# Sheet1.net
KiCad netlist of a schematic drawn in Altium Designer
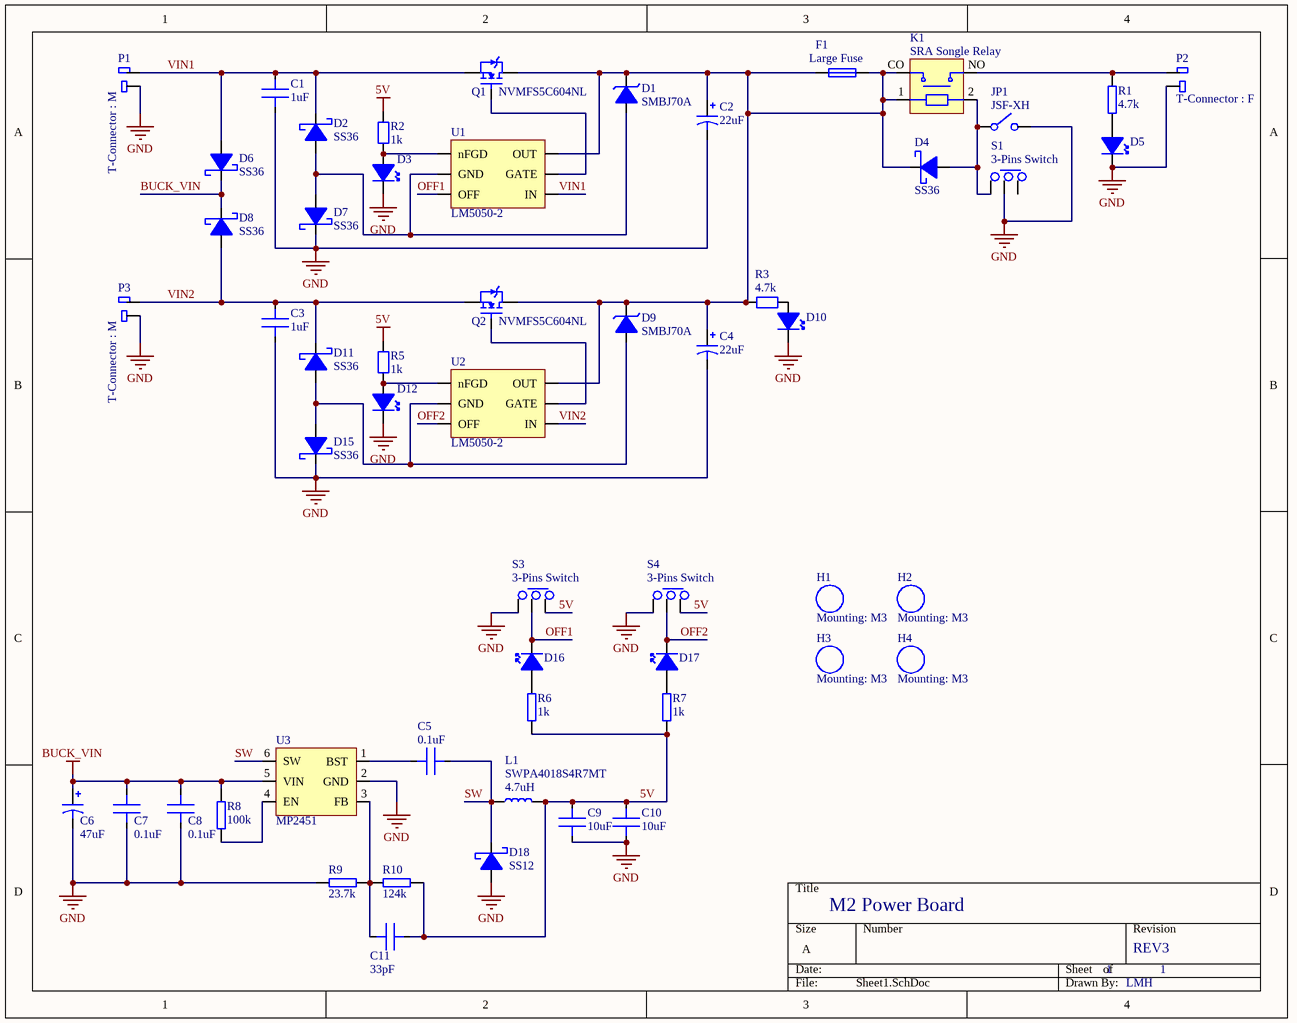
[diagram p0: Sheet1.SchDoc]

(export (version "E")
  (design (tool "Eeschema 10.0.6"))
  (components
    (comp (ref "C1")
      (value "1uF")
      (footprint "CAP 0805/2012")
      (description "Unpolarized Capacitor")
      (fields (field (name "Comment") "Cap : Unpolarized"))
      (libsource (lib "MyLib_General") (part "Cap {colon} Unpolarized"))
    )
    (comp (ref "C2")
      (value "22uF")
      (footprint "CAP AL C 5.3MM")
      (description "Polarized Capacitor")
      (fields (field (name "Comment") "Cap : Polarized"))
      (libsource (lib "") (part "Cap {colon} Polarized_1"))
    )
    (comp (ref "C3")
      (value "1uF")
      (footprint "CAP 0805/2012")
      (description "Unpolarized Capacitor")
      (fields (field (name "Comment") "Cap : Unpolarized"))
      (libsource (lib "MyLib_General") (part "Cap {colon} Unpolarized"))
    )
    (comp (ref "C4")
      (value "22uF")
      (footprint "CAP AL C 5.3MM")
      (description "Polarized Capacitor")
      (fields (field (name "Comment") "Cap : Polarized"))
      (libsource (lib "") (part "Cap {colon} Polarized_1"))
    )
    (comp (ref "C5")
      (value "0.1uF")
      (footprint "CAP 0805/2012")
      (description "Unpolarized Capacitor")
      (fields (field (name "Comment") "Cap : Unpolarized"))
      (libsource (lib "MyLib_General") (part "Cap {colon} Unpolarized"))
    )
    (comp (ref "C6")
      (value "47uF")
      (footprint "CAP AL D 6.6MM")
      (description "Polarized Capacitor")
      (fields (field (name "Comment") "Cap : Polarized"))
      (libsource (lib "MyLib_General") (part "Cap {colon} Polarized"))
    )
    (comp (ref "C7")
      (value "0.1uF")
      (footprint "CAP 0805/2012")
      (description "Unpolarized Capacitor")
      (fields (field (name "Comment") "Cap : Unpolarized"))
      (libsource (lib "MyLib_General") (part "Cap {colon} Unpolarized"))
    )
    (comp (ref "C8")
      (value "0.1uF")
      (footprint "CAP 0805/2012")
      (description "Unpolarized Capacitor")
      (fields (field (name "Comment") "Cap : Unpolarized"))
      (libsource (lib "MyLib_General") (part "Cap {colon} Unpolarized"))
    )
    (comp (ref "C9")
      (value "10uF")
      (footprint "CAP 1206/3216")
      (description "Unpolarized Capacitor")
      (fields (field (name "Comment") "Cap : Unpolarized"))
      (libsource (lib "MyLib_General") (part "Cap {colon} Unpolarized"))
    )
    (comp (ref "C10")
      (value "10uF")
      (footprint "CAP 1206/3216")
      (description "Unpolarized Capacitor")
      (fields (field (name "Comment") "Cap : Unpolarized"))
      (libsource (lib "MyLib_General") (part "Cap {colon} Unpolarized"))
    )
    (comp (ref "C11")
      (value "33pF")
      (footprint "CAP 0805/2012")
      (description "Unpolarized Capacitor")
      (fields (field (name "Comment") "Cap : Unpolarized"))
      (libsource (lib "MyLib_General") (part "Cap {colon} Unpolarized"))
    )
    (comp (ref "D1")
      (value "SMBJ70A")
      (footprint "SMB (DO-214AA)")
      (description "Transient Voltage Suppression Diodes")
      (fields (field (name "NAME") "SMBJ70A"))
      (libsource (lib "Schlib1") (part "SMBJ70A"))
    )
    (comp (ref "D2")
      (value "SS36")
      (footprint "SMA (DO-214AC)")
      (description "Surface Mount Schottky Barrier Rectifier")
      (fields (field (name "NAME") "SS36"))
      (libsource (lib "Schlib1") (part "SS36"))
    )
    (comp (ref "D3") (value "LED") (footprint "LED 0805/2012") (libsource (lib "MyLib_General") (part "LED")))
    (comp (ref "D4")
      (value "SS36")
      (footprint "SMA (DO-214AC)")
      (description "Surface Mount Schottky Barrier Rectifier")
      (fields (field (name "NAME") "SS36"))
      (libsource (lib "Schlib1") (part "SS36"))
    )
    (comp (ref "D5") (value "LED") (footprint "LED 0805/2012") (libsource (lib "MyLib_General") (part "LED")))
    (comp (ref "D6")
      (value "SS36")
      (footprint "SMA (DO-214AC)")
      (description "Surface Mount Schottky Barrier Rectifier")
      (fields (field (name "NAME") "SS36"))
      (libsource (lib "Schlib1") (part "SS36"))
    )
    (comp (ref "D7")
      (value "SS36")
      (footprint "SMA (DO-214AC)")
      (description "Surface Mount Schottky Barrier Rectifier")
      (fields (field (name "NAME") "SS36"))
      (libsource (lib "Schlib1") (part "SS36"))
    )
    (comp (ref "D8")
      (value "SS36")
      (footprint "SMA (DO-214AC)")
      (description "Surface Mount Schottky Barrier Rectifier")
      (fields (field (name "NAME") "SS36"))
      (libsource (lib "Schlib1") (part "SS36"))
    )
    (comp (ref "D9")
      (value "SMBJ70A")
      (footprint "SMB (DO-214AA)")
      (description "Transient Voltage Suppression Diodes")
      (fields (field (name "NAME") "SMBJ70A"))
      (libsource (lib "Schlib1") (part "SMBJ70A"))
    )
    (comp (ref "D10")
      (value "LED")
      (footprint "LED 0805/2012")
      (libsource (lib "MyLib_General") (part "LED"))
    )
    (comp (ref "D11")
      (value "SS36")
      (footprint "SMA (DO-214AC)")
      (description "Surface Mount Schottky Barrier Rectifier")
      (fields (field (name "NAME") "SS36"))
      (libsource (lib "Schlib1") (part "SS36"))
    )
    (comp (ref "D12")
      (value "LED")
      (footprint "LED 0805/2012")
      (libsource (lib "MyLib_General") (part "LED"))
    )
    (comp (ref "D15")
      (value "SS36")
      (footprint "SMA (DO-214AC)")
      (description "Surface Mount Schottky Barrier Rectifier")
      (fields (field (name "NAME") "SS36"))
      (libsource (lib "Schlib1") (part "SS36"))
    )
    (comp (ref "D16")
      (value "LED")
      (footprint "LED 0805/2012")
      (libsource (lib "MyLib_General") (part "LED"))
    )
    (comp (ref "D17")
      (value "LED")
      (footprint "LED 0805/2012")
      (libsource (lib "MyLib_General") (part "LED"))
    )
    (comp (ref "D18")
      (value "SS12")
      (footprint "SMA (DO-214AC)")
      (description "Surface Mount Schottky Barrier Rectifier")
      (fields (field (name "NAME") "SS12"))
      (libsource (lib "Schlib1") (part "SS12"))
    )
    (comp (ref "F1")
      (value "Large Fuse")
      (footprint "Fuse")
      (description "Large size fuse")
      (libsource (lib "Schlib1") (part "Large Fuse"))
    )
    (comp (ref "H1")
      (value "Mounting: M3")
      (footprint "Mounting hole M3")
      (description "Mounting Hole: M3")
      (libsource (lib "MyLib_General") (part "Mounting{colon} M3"))
    )
    (comp (ref "H2")
      (value "Mounting: M3")
      (footprint "Mounting hole M3")
      (description "Mounting Hole: M3")
      (libsource (lib "MyLib_General") (part "Mounting{colon} M3"))
    )
    (comp (ref "H3")
      (value "Mounting: M3")
      (footprint "Mounting hole M3")
      (description "Mounting Hole: M3")
      (libsource (lib "MyLib_General") (part "Mounting{colon} M3"))
    )
    (comp (ref "H4")
      (value "Mounting: M3")
      (footprint "Mounting hole M3")
      (description "Mounting Hole: M3")
      (libsource (lib "MyLib_General") (part "Mounting{colon} M3"))
    )
    (comp (ref "JP1")
      (value "2-Pins Header")
      (footprint "2-Pins Header")
      (fields (field (name "NAME") "JSF-XH"))
      (libsource (lib "Schlib1") (part "2-Pins Header"))
    )
    (comp (ref "K1")
      (value "SRA Songle Relay")
      (footprint "SRA Songle Relay")
      (description "20A Relay")
      (libsource (lib "Schlib1") (part "SRA Songle Relay"))
    )
    (comp (ref "L1")
      (value "SWPA4018S4R7MT")
      (footprint "SWPA4018S4R7MT")
      (description "Wire Wound SMD Power Inductor ; 4.7uH ; 1.7A")
      (fields (field (name "ALTIUM_VALUE") "4.7uH"))
      (libsource (lib "Schlib1") (part "SWPA4018S4R7MT"))
    )
    (comp (ref "P1")
      (value "T-Connector : M")
      (footprint "T CONNECTOR M")
      (description "T-shape connector ; Male side")
      (fields (field (name "NAME") "T-Connector : M"))
      (libsource (lib "MyLib_General") (part "T-Connector {colon} M"))
    )
    (comp (ref "P2")
      (value "T-Connector : F")
      (footprint "T CONNECTOR F")
      (description "T-shape connector ; Female side")
      (fields (field (name "NAME") "T-Connector : F"))
      (libsource (lib "MyLib_General") (part "T-Connector {colon} F"))
    )
    (comp (ref "P3")
      (value "T-Connector : M")
      (footprint "T CONNECTOR M")
      (description "T-shape connector ; Male side")
      (fields (field (name "NAME") "T-Connector : M"))
      (libsource (lib "MyLib_General") (part "T-Connector {colon} M"))
    )
    (comp (ref "Q1")
      (value "NVMFS5C604NL")
      (footprint "NVMFS5C604NL")
      (description "Power MOSFET ; 60 V ; 1.2 mR ; 287A ; Single N−Channel")
      (fields (field (name "NAME") "NVMFS5C604NL"))
      (libsource (lib "Schlib1") (part "NVMFS5C604NL"))
    )
    (comp (ref "Q2")
      (value "NVMFS5C604NL")
      (footprint "NVMFS5C604NL")
      (description "Power MOSFET ; 60 V ; 1.2 mR ; 287A ; Single N−Channel")
      (fields (field (name "NAME") "NVMFS5C604NL"))
      (libsource (lib "Schlib1") (part "NVMFS5C604NL"))
    )
    (comp (ref "R1")
      (value "4.7k")
      (footprint "RES 0805/2012")
      (description "Resistor")
      (fields (field (name "Comment") "Res"))
      (libsource (lib "MyLib_General") (part "Res"))
    )
    (comp (ref "R2")
      (value "1k")
      (footprint "RES 0805/2012")
      (description "Resistor")
      (fields (field (name "Comment") "Res"))
      (libsource (lib "") (part "Res_1"))
    )
    (comp (ref "R3")
      (value "4.7k")
      (footprint "RES 0805/2012")
      (description "Resistor")
      (fields (field (name "Comment") "Res"))
      (libsource (lib "") (part "Res_1"))
    )
    (comp (ref "R5")
      (value "1k")
      (footprint "RES 0805/2012")
      (description "Resistor")
      (fields (field (name "Comment") "Res"))
      (libsource (lib "") (part "Res_1"))
    )
    (comp (ref "R6")
      (value "1k")
      (footprint "RES 0805/2012")
      (description "Resistor")
      (fields (field (name "Comment") "Res"))
      (libsource (lib "MyLib_General") (part "Res"))
    )
    (comp (ref "R7")
      (value "1k")
      (footprint "RES 0805/2012")
      (description "Resistor")
      (fields (field (name "Comment") "Res"))
      (libsource (lib "MyLib_General") (part "Res"))
    )
    (comp (ref "R8")
      (value "100k")
      (footprint "RES 0805/2012")
      (description "Resistor")
      (fields (field (name "Comment") "Res"))
      (libsource (lib "MyLib_General") (part "Res"))
    )
    (comp (ref "R9")
      (value "23.7k")
      (footprint "RES 0805/2012")
      (description "Resistor")
      (fields (field (name "Comment") "Res"))
      (libsource (lib "MyLib_General") (part "Res"))
    )
    (comp (ref "R10")
      (value "124k")
      (footprint "RES 0805/2012")
      (description "Resistor")
      (fields (field (name "Comment") "Res"))
      (libsource (lib "MyLib_General") (part "Res"))
    )
    (comp (ref "S1")
      (value "3-Pins Switch")
      (footprint "3-Pins Switch")
      (description "SS12d00G3")
      (fields (field (name "NAME") "3-Pins Switch"))
      (libsource (lib "Schlib1") (part "3-Pins Switch"))
    )
    (comp (ref "S3")
      (value "3-Pins Switch")
      (footprint "3-Pins Switch")
      (description "SS12d00G3")
      (fields (field (name "NAME") "3-Pins Switch"))
      (libsource (lib "Schlib1") (part "3-Pins Switch"))
    )
    (comp (ref "S4")
      (value "3-Pins Switch")
      (footprint "3-Pins Switch")
      (description "SS12d00G3")
      (fields (field (name "NAME") "3-Pins Switch"))
      (libsource (lib "Schlib1") (part "3-Pins Switch"))
    )
    (comp (ref "U1")
      (value "LM5050-2")
      (footprint "SOT23-6")
      (description "High-Side OR-ing FET Controller")
      (fields (field (name "NAME") "LM5050-2"))
      (libsource (lib "Schlib1") (part "LM5050-2"))
    )
    (comp (ref "U2")
      (value "LM5050-2")
      (footprint "SOT23-6")
      (description "High-Side OR-ing FET Controller")
      (fields (field (name "NAME") "LM5050-2"))
      (libsource (lib "Schlib1") (part "LM5050-2"))
    )
    (comp (ref "U3")
      (value "MP2451")
      (footprint "SOT23-6")
      (description "Step-Down Converter ; 36V ; 2MHz ; 0.6A")
      (fields (field (name "NAME") "MP2451"))
      (libsource (lib "Schlib1") (part "MP2451"))
    )
  )
  (nets
    (net (code "1") (name "/OFF1") (class "Default")
      (node (ref "D16") (pin "K") (pinfunction "K_K") (pintype "passive"))
      (node (ref "S3") (pin "2") (pintype "passive"))
      (node (ref "U1") (pin "3") (pinfunction "OFF_3") (pintype "passive"))
    )
    (net (code "2") (name "/OFF2") (class "Default")
      (node (ref "D17") (pin "K") (pinfunction "K_K") (pintype "passive"))
      (node (ref "S4") (pin "2") (pintype "passive"))
      (node (ref "U2") (pin "3") (pinfunction "OFF_3") (pintype "passive"))
    )
    (net (code "3") (name "/SW") (class "Default")
      (node (ref "C5") (pin "2") (pinfunction "2_2") (pintype "passive"))
      (node (ref "D18") (pin "K") (pinfunction "K_K") (pintype "passive"))
      (node (ref "L1") (pin "1") (pinfunction "1_1") (pintype "passive"))
      (node (ref "U3") (pin "6") (pinfunction "SW_6") (pintype "passive"))
    )
    (net (code "4") (name "/VIN1") (class "Default")
      (node (ref "C1") (pin "2") (pinfunction "2_2") (pintype "passive"))
      (node (ref "D2") (pin "K") (pinfunction "K_K") (pintype "passive"))
      (node (ref "D6") (pin "A") (pinfunction "A_A") (pintype "passive"))
      (node (ref "P1") (pin "P") (pinfunction "2_P") (pintype "passive"))
      (node (ref "Q1") (pin "S") (pinfunction "S_S") (pintype "passive"))
      (node (ref "U1") (pin "4") (pinfunction "IN_4") (pintype "passive"))
    )
    (net (code "5") (name "/VIN2") (class "Default")
      (node (ref "C3") (pin "2") (pinfunction "2_2") (pintype "passive"))
      (node (ref "D11") (pin "K") (pinfunction "K_K") (pintype "passive"))
      (node (ref "D8") (pin "A") (pinfunction "A_A") (pintype "passive"))
      (node (ref "P3") (pin "P") (pinfunction "2_P") (pintype "passive"))
      (node (ref "Q2") (pin "S") (pinfunction "S_S") (pintype "passive"))
      (node (ref "U2") (pin "4") (pinfunction "IN_4") (pintype "passive"))
    )
    (net (code "6") (name "5V") (class "Default")
      (node (ref "C10") (pin "2") (pinfunction "2_2") (pintype "passive"))
      (node (ref "C11") (pin "2") (pinfunction "2_2") (pintype "passive"))
      (node (ref "C9") (pin "2") (pinfunction "2_2") (pintype "passive"))
      (node (ref "L1") (pin "2") (pinfunction "2_2") (pintype "passive"))
      (node (ref "R10") (pin "2") (pinfunction "1_2") (pintype "passive"))
      (node (ref "R2") (pin "2") (pinfunction "1_2") (pintype "passive"))
      (node (ref "R5") (pin "2") (pinfunction "1_2") (pintype "passive"))
      (node (ref "R6") (pin "1") (pinfunction "1_1") (pintype "passive"))
      (node (ref "R7") (pin "1") (pinfunction "1_1") (pintype "passive"))
      (node (ref "S3") (pin "3") (pintype "passive"))
      (node (ref "S4") (pin "3") (pintype "passive"))
    )
    (net (code "7") (name "BUCK_VIN") (class "Default")
      (node (ref "C6") (pin "A") (pinfunction "A_A") (pintype "passive"))
      (node (ref "C7") (pin "2") (pinfunction "2_2") (pintype "passive"))
      (node (ref "C8") (pin "2") (pinfunction "2_2") (pintype "passive"))
      (node (ref "D6") (pin "K") (pinfunction "K_K") (pintype "passive"))
      (node (ref "D8") (pin "K") (pinfunction "K_K") (pintype "passive"))
      (node (ref "R8") (pin "2") (pinfunction "1_2") (pintype "passive"))
      (node (ref "U3") (pin "5") (pinfunction "VIN_5") (pintype "passive"))
    )
    (net (code "8") (name "GND") (class "Default")
      (node (ref "C1") (pin "1") (pinfunction "1_1") (pintype "passive"))
      (node (ref "C10") (pin "1") (pinfunction "1_1") (pintype "passive"))
      (node (ref "C2") (pin "K") (pinfunction "K_K") (pintype "passive"))
      (node (ref "C3") (pin "1") (pinfunction "1_1") (pintype "passive"))
      (node (ref "C4") (pin "K") (pinfunction "K_K") (pintype "passive"))
      (node (ref "C6") (pin "K") (pinfunction "K_K") (pintype "passive"))
      (node (ref "C7") (pin "1") (pinfunction "1_1") (pintype "passive"))
      (node (ref "C8") (pin "1") (pinfunction "1_1") (pintype "passive"))
      (node (ref "C9") (pin "1") (pinfunction "1_1") (pintype "passive"))
      (node (ref "D10") (pin "K") (pinfunction "K_K") (pintype "passive"))
      (node (ref "D12") (pin "K") (pinfunction "K_K") (pintype "passive"))
      (node (ref "D15") (pin "K") (pinfunction "K_K") (pintype "passive"))
      (node (ref "D18") (pin "A") (pinfunction "A_A") (pintype "passive"))
      (node (ref "D3") (pin "K") (pinfunction "K_K") (pintype "passive"))
      (node (ref "D5") (pin "K") (pinfunction "K_K") (pintype "passive"))
      (node (ref "D7") (pin "K") (pinfunction "K_K") (pintype "passive"))
      (node (ref "JP1") (pin "2") (pinfunction "2_2") (pintype "passive"))
      (node (ref "P1") (pin "N") (pinfunction "2_N") (pintype "passive"))
      (node (ref "P2") (pin "N") (pinfunction "-_N") (pintype "passive"))
      (node (ref "P3") (pin "N") (pinfunction "2_N") (pintype "passive"))
      (node (ref "R9") (pin "1") (pinfunction "1_1") (pintype "passive"))
      (node (ref "S1") (pin "2") (pintype "passive"))
      (node (ref "S3") (pin "1") (pintype "passive"))
      (node (ref "S4") (pin "1") (pintype "passive"))
      (node (ref "U3") (pin "2") (pinfunction "GND_2") (pintype "passive"))
    )
    (net (code "9") (name "Net-(D5-PadA)") (class "Default")
      (node (ref "D5") (pin "A") (pinfunction "A_A") (pintype "passive"))
      (node (ref "R1") (pin "1") (pinfunction "1_1") (pintype "passive"))
    )
    (net (code "10") (name "Net-(D10-PadA)") (class "Default")
      (node (ref "D10") (pin "A") (pinfunction "A_A") (pintype "passive"))
      (node (ref "R3") (pin "1") (pinfunction "1_1") (pintype "passive"))
    )
    (net (code "11") (name "Net-(D16-PadA)") (class "Default")
      (node (ref "D16") (pin "A") (pinfunction "A_A") (pintype "passive"))
      (node (ref "R6") (pin "2") (pinfunction "1_2") (pintype "passive"))
    )
    (net (code "12") (name "Net-(D17-PadA)") (class "Default")
      (node (ref "D17") (pin "A") (pinfunction "A_A") (pintype "passive"))
      (node (ref "R7") (pin "2") (pinfunction "1_2") (pintype "passive"))
    )
    (net (code "13") (name "Net-(K1-Coil1)") (class "Default")
      (node (ref "C2") (pin "A") (pinfunction "A_A") (pintype "passive"))
      (node (ref "C4") (pin "A") (pinfunction "A_A") (pintype "passive"))
      (node (ref "D1") (pin "K") (pinfunction "K_K") (pintype "passive"))
      (node (ref "D4") (pin "K") (pinfunction "K_K") (pintype "passive"))
      (node (ref "D9") (pin "K") (pinfunction "K_K") (pintype "passive"))
      (node (ref "F1") (pin "1") (pinfunction "1_1") (pintype "passive"))
      (node (ref "F1") (pin "2") (pinfunction "2_2") (pintype "passive"))
      (node (ref "K1") (pin "1") (pinfunction "Coil1_1") (pintype "passive"))
      (node (ref "K1") (pin "CO") (pinfunction "Relay1_CO") (pintype "passive"))
      (node (ref "Q1") (pin "D") (pinfunction "D_D") (pintype "passive"))
      (node (ref "Q2") (pin "D") (pinfunction "D_D") (pintype "passive"))
      (node (ref "R3") (pin "2") (pinfunction "1_2") (pintype "passive"))
      (node (ref "U1") (pin "6") (pinfunction "OUT_6") (pintype "passive"))
      (node (ref "U2") (pin "6") (pinfunction "OUT_6") (pintype "passive"))
    )
    (net (code "14") (name "Net-(K1-Coil2)") (class "Default")
      (node (ref "D4") (pin "A") (pinfunction "A_A") (pintype "passive"))
      (node (ref "JP1") (pin "1") (pinfunction "1_1") (pintype "passive"))
      (node (ref "K1") (pin "2") (pinfunction "Coil2_2") (pintype "passive"))
      (node (ref "S1") (pin "1") (pintype "passive"))
    )
    (net (code "15") (name "Net-(K1-Relay2)") (class "Default")
      (node (ref "K1") (pin "NO") (pinfunction "Relay2_NO") (pintype "passive"))
      (node (ref "P2") (pin "P") (pinfunction "+_P") (pintype "passive"))
      (node (ref "R1") (pin "2") (pinfunction "1_2") (pintype "passive"))
    )
    (net (code "16") (name "Net-(U1-GATE)") (class "Default")
      (node (ref "Q1") (pin "G") (pinfunction "G_G") (pintype "passive"))
      (node (ref "U1") (pin "5") (pinfunction "GATE_5") (pintype "passive"))
    )
    (net (code "17") (name "Net-(U1-GND)") (class "Default")
      (node (ref "D1") (pin "A") (pinfunction "A_A") (pintype "passive"))
      (node (ref "D2") (pin "A") (pinfunction "A_A") (pintype "passive"))
      (node (ref "D7") (pin "A") (pinfunction "A_A") (pintype "passive"))
      (node (ref "U1") (pin "2") (pinfunction "GND_2") (pintype "passive"))
    )
    (net (code "18") (name "Net-(U1-nFGD)") (class "Default")
      (node (ref "D3") (pin "A") (pinfunction "A_A") (pintype "passive"))
      (node (ref "R2") (pin "1") (pinfunction "1_1") (pintype "passive"))
      (node (ref "U1") (pin "1") (pinfunction "nFGD_1") (pintype "passive"))
    )
    (net (code "19") (name "Net-(U2-GATE)") (class "Default")
      (node (ref "Q2") (pin "G") (pinfunction "G_G") (pintype "passive"))
      (node (ref "U2") (pin "5") (pinfunction "GATE_5") (pintype "passive"))
    )
    (net (code "20") (name "Net-(U2-GND)") (class "Default")
      (node (ref "D11") (pin "A") (pinfunction "A_A") (pintype "passive"))
      (node (ref "D15") (pin "A") (pinfunction "A_A") (pintype "passive"))
      (node (ref "D9") (pin "A") (pinfunction "A_A") (pintype "passive"))
      (node (ref "U2") (pin "2") (pinfunction "GND_2") (pintype "passive"))
    )
    (net (code "21") (name "Net-(U2-nFGD)") (class "Default")
      (node (ref "D12") (pin "A") (pinfunction "A_A") (pintype "passive"))
      (node (ref "R5") (pin "1") (pinfunction "1_1") (pintype "passive"))
      (node (ref "U2") (pin "1") (pinfunction "nFGD_1") (pintype "passive"))
    )
    (net (code "22") (name "Net-(U3-BST)") (class "Default")
      (node (ref "C5") (pin "1") (pinfunction "1_1") (pintype "passive"))
      (node (ref "U3") (pin "1") (pinfunction "BST_1") (pintype "passive"))
    )
    (net (code "23") (name "Net-(U3-EN)") (class "Default")
      (node (ref "R8") (pin "1") (pinfunction "1_1") (pintype "passive"))
      (node (ref "U3") (pin "4") (pinfunction "EN_4") (pintype "passive"))
    )
    (net (code "24") (name "Net-(U3-FB)") (class "Default")
      (node (ref "C11") (pin "1") (pinfunction "1_1") (pintype "passive"))
      (node (ref "R10") (pin "1") (pinfunction "1_1") (pintype "passive"))
      (node (ref "R9") (pin "2") (pinfunction "1_2") (pintype "passive"))
      (node (ref "U3") (pin "3") (pinfunction "FB_3") (pintype "passive"))
    )
    (net (code "25") (name "unconnected-(S1-Pad3)") (class "Default")
      (node (ref "S1") (pin "3") (pintype "passive"))
    )
  )
)
